# Arduino-RedBoard.net
KiCad netlist of a schematic drawn in Altium Designer
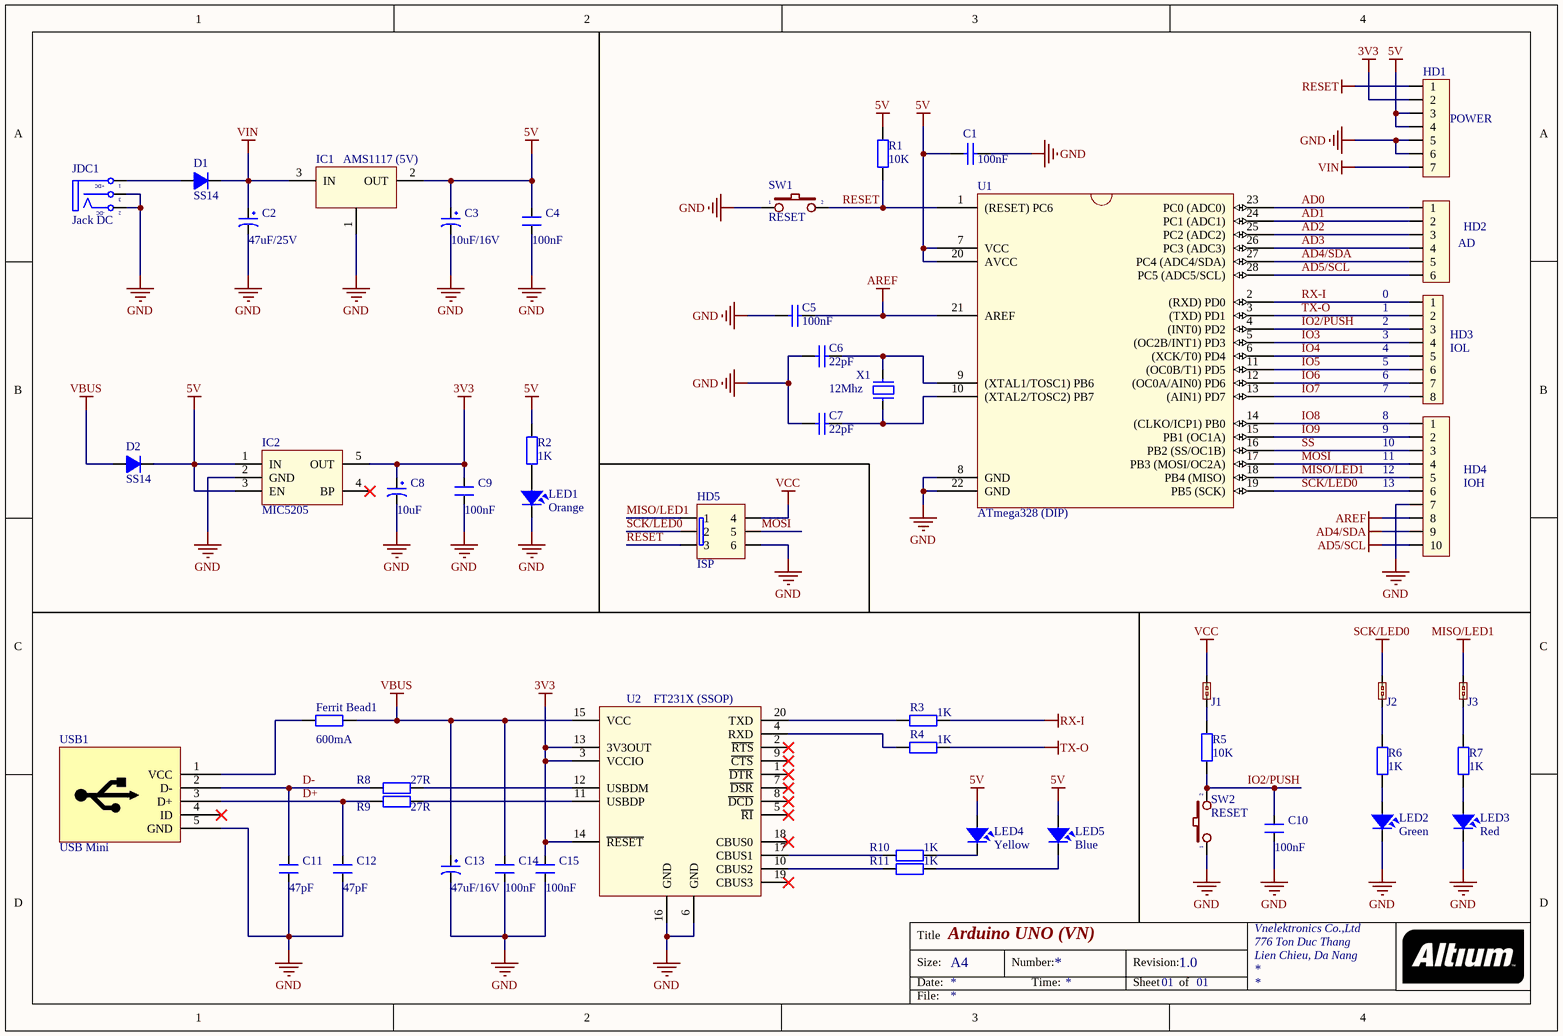
[diagram p0: Arduino-RedBoard.SchDoc]

(export (version "E")
  (design (tool "Eeschema 10.0.6"))
  (components
    (comp (ref "C1")
      (value "100nF")
      (footprint "C0603")
      (description "CAP NPO CAPNTO 1nF 100V 10%")
      (fields (field (name "Comment") "5AK102KABAA"))
      (libsource (lib "lpson") (part "5AK102KABAA"))
    )
    (comp (ref "C2") (value "47uF/25V") (footprint "C_FK_47UF_25V") (libsource (lib "VNELEK") (part "CP1")))
    (comp (ref "C3")
      (value "10uF/16V")
      (footprint "C0805")
      (description "Cap P  0,1uF < 22uF , 16 - 50V")
      (libsource (lib "VNELEK") (part "CP1"))
    )
    (comp (ref "C4")
      (value "100nF")
      (footprint "C0603")
      (description "Cap np 104 => 105pF")
      (libsource (lib "VNELEK") (part "CN2"))
    )
    (comp (ref "C5")
      (value "100nF")
      (footprint "C0603")
      (description "CAP NPO CAPNTO 1nF 100V 10%")
      (fields (field (name "Comment") "5AK102KABAA"))
      (libsource (lib "lpson") (part "5AK102KABAA"))
    )
    (comp (ref "C6")
      (value "22pF")
      (footprint "C0603")
      (description "CAP NPO CAPNTO 1nF 100V 10%")
      (fields (field (name "Comment") "5AK102KABAA"))
      (libsource (lib "lpson") (part "5AK102KABAA"))
    )
    (comp (ref "C7")
      (value "22pF")
      (footprint "C0603")
      (description "CAP NPO CAPNTO 1nF 100V 10%")
      (fields (field (name "Comment") "5AK102KABAA"))
      (libsource (lib "lpson") (part "5AK102KABAA"))
    )
    (comp (ref "C8")
      (value "10uF")
      (footprint "C0805")
      (description "Cap P  0,1uF < 22uF , 16 - 50V")
      (libsource (lib "VNELEK") (part "CP1"))
    )
    (comp (ref "C9")
      (value "100nF")
      (footprint "C0603")
      (description "Cap np 104 => 105pF")
      (libsource (lib "VNELEK") (part "CN2"))
    )
    (comp (ref "C10")
      (value "100nF")
      (footprint "C0603")
      (description "Cap np 104 => 105pF")
      (libsource (lib "VNELEK") (part "CN2"))
    )
    (comp (ref "C11")
      (value "47pF")
      (footprint "C0805")
      (description "Cap np 104 => 105pF")
      (libsource (lib "VNELEK") (part "CN2"))
    )
    (comp (ref "C12")
      (value "47pF")
      (footprint "C0805")
      (description "Cap np 104 => 105pF")
      (libsource (lib "VNELEK") (part "CN2"))
    )
    (comp (ref "C13") (value "47uF/16V") (footprint "C_FK_47UF_16V") (libsource (lib "VNELEK") (part "CP1")))
    (comp (ref "C14")
      (value "100nF")
      (footprint "C0603")
      (description "Cap np 104 => 105pF")
      (libsource (lib "VNELEK") (part "CN2"))
    )
    (comp (ref "C15")
      (value "100nF")
      (footprint "C0603")
      (description "Cap np 104 => 105pF")
      (libsource (lib "VNELEK") (part "CN2"))
    )
    (comp (ref "D1")
      (value "SS14")
      (footprint "SS14")
      (description "Diode 1A")
      (libsource (lib "VNELEK") (part "D1A"))
    )
    (comp (ref "D2")
      (value "SS14")
      (footprint "SS14")
      (description "Diode 1A")
      (libsource (lib "VNELEK") (part "D1A"))
    )
    (comp (ref "Ferrit Bead1")
      (value "600mA")
      (footprint "CB2012")
      (description "Ferrit Bead")
      (libsource (lib "") (part "Res2_2"))
    )
    (comp (ref "HD1")
      (value "POWER")
      (footprint "Header_7")
      (description "Header 7")
      (libsource (lib "Tran Tuan") (part "Hed7"))
    )
    (comp (ref "HD2")
      (value "AD")
      (footprint "Header_6")
      (description "Header 6")
      (libsource (lib "Tran Tuan") (part "Hed6"))
    )
    (comp (ref "HD3")
      (value "IOL")
      (footprint "Header_8")
      (description "Hedear 8")
      (fields (field (name "CREAT BY") "VanDungEvn@Gmail.com"))
      (libsource (lib "VNELEK") (part "Hed8"))
    )
    (comp (ref "HD4")
      (value "IOH")
      (footprint "Header_10")
      (description "Header 10")
      (libsource (lib "Tran Tuan") (part "Hed10"))
    )
    (comp (ref "HD5")
      (value "ISP")
      (footprint "Header_3x2")
      (description "Header 3x2")
      (libsource (lib "Tran Tuan") (part "HED3x2"))
    )
    (comp (ref "IC1")
      (value "AMS1117 (5V)")
      (footprint "AMS1117-5.0V")
      (description "1A LOW DROPOUT VOLTAGE REGULATOR")
      (libsource (lib "Tran Tuan") (part "AMS1117"))
    )
    (comp (ref "IC2")
      (value "MIC5205")
      (footprint "MIC5205")
      (description "150mA Low  -  Noise LDO Regulator")
      (libsource (lib "Tran Tuan") (part "MIC5205"))
    )
    (comp (ref "J1")
      (value "Short Jump")
      (footprint "Header_2")
      (libsource (lib "Tran Tuan") (part "ShortJump"))
    )
    (comp (ref "J2")
      (value "Short Jump")
      (footprint "Header_2")
      (libsource (lib "Tran Tuan") (part "ShortJump"))
    )
    (comp (ref "J3")
      (value "Short Jump")
      (footprint "Header_2")
      (libsource (lib "Tran Tuan") (part "ShortJump"))
    )
    (comp (ref "JDC1")
      (value "Jack DC")
      (footprint "DC-IN")
      (description "Jac DC input")
      (libsource (lib "VNELEK") (part "DCIN"))
    )
    (comp (ref "LED1")
      (value "Orange")
      (footprint "Led 0805Y")
      (description "LED Single colour Green and Red")
      (libsource (lib "VNELEK") (part "LED"))
    )
    (comp (ref "LED2")
      (value "Green")
      (footprint "Led 0805G")
      (description "LED Single colour Green and Red")
      (libsource (lib "VNELEK") (part "LED"))
    )
    (comp (ref "LED3")
      (value "Red")
      (footprint "Led 0805R")
      (description "LED Single colour Green and Red")
      (libsource (lib "VNELEK") (part "LED"))
    )
    (comp (ref "LED4")
      (value "Yellow")
      (footprint "Led 0805Y")
      (description "LED Single colour Green and Red")
      (libsource (lib "VNELEK") (part "LED"))
    )
    (comp (ref "LED5")
      (value "Blue")
      (footprint "Led 0805BL")
      (description "LED Single colour Green and Red")
      (libsource (lib "VNELEK") (part "LED"))
    )
    (comp (ref "R1")
      (value "10K")
      (footprint "RESC2012L")
      (description "Resistor")
      (fields (field (name "Comment") "Res2") (field (name "PUBLISHER") "Altium Limited"))
      (libsource (lib "Miscellaneous Devices") (part "Res2"))
    )
    (comp (ref "R2")
      (value "1K")
      (footprint "RESC2012L")
      (description "Resistor")
      (fields (field (name "Comment") "Res2") (field (name "PUBLISHER") "Altium Limited"))
      (libsource (lib "Miscellaneous Devices") (part "Res2"))
    )
    (comp (ref "R3")
      (value "1K")
      (footprint "RESC2012L")
      (description "Resistor")
      (fields (field (name "Comment") "Res2") (field (name "PUBLISHER") "Altium Limited"))
      (libsource (lib "") (part "Res2_2"))
    )
    (comp (ref "R4")
      (value "1K")
      (footprint "RESC2012L")
      (description "Resistor")
      (fields (field (name "Comment") "Res2") (field (name "PUBLISHER") "Altium Limited"))
      (libsource (lib "") (part "Res2_2"))
    )
    (comp (ref "R5")
      (value "10K")
      (footprint "RESC2012L")
      (description "Resistor")
      (fields (field (name "Comment") "Res2") (field (name "PUBLISHER") "Altium Limited"))
      (libsource (lib "Miscellaneous Devices") (part "Res2"))
    )
    (comp (ref "R6")
      (value "1K")
      (footprint "RESC2012L")
      (description "Resistor")
      (fields (field (name "Comment") "Res2") (field (name "PUBLISHER") "Altium Limited"))
      (libsource (lib "Miscellaneous Devices") (part "Res2"))
    )
    (comp (ref "R7")
      (value "1K")
      (footprint "RESC2012L")
      (description "Resistor")
      (fields (field (name "Comment") "Res2") (field (name "PUBLISHER") "Altium Limited"))
      (libsource (lib "Miscellaneous Devices") (part "Res2"))
    )
    (comp (ref "R8")
      (value "27R")
      (footprint "RESC2012L")
      (description "Resistor")
      (fields (field (name "Comment") "Res2") (field (name "PUBLISHER") "Altium Limited"))
      (libsource (lib "") (part "Res2_1"))
    )
    (comp (ref "R9")
      (value "27R")
      (footprint "RESC2012L")
      (description "Resistor")
      (fields (field (name "Comment") "Res2") (field (name "PUBLISHER") "Altium Limited"))
      (libsource (lib "") (part "Res2_1"))
    )
    (comp (ref "R10")
      (value "1K")
      (footprint "RESC2012L")
      (description "Resistor")
      (fields (field (name "Comment") "Res2") (field (name "PUBLISHER") "Altium Limited"))
      (libsource (lib "") (part "Res2_1"))
    )
    (comp (ref "R11")
      (value "1K")
      (footprint "RESC2012L")
      (description "Resistor")
      (fields (field (name "Comment") "Res2") (field (name "PUBLISHER") "Altium Limited"))
      (libsource (lib "") (part "Res2_1"))
    )
    (comp (ref "SW1")
      (value "RESET")
      (footprint "BUTTON 2PIN TRON")
      (description "Switch button 2 pin")
      (libsource (lib "VNELEK") (part "SW2"))
    )
    (comp (ref "SW2")
      (value "RESET")
      (footprint "BUTTON 2PIN TRON")
      (description "Switch button 2 pin")
      (libsource (lib "VNELEK") (part "SW2"))
    )
    (comp (ref "U1")
      (value "ATmega328 (DIP)")
      (footprint "ATmega328 (DIP)")
      (description "Atmel 8-bit Microcontroller")
      (libsource (lib "Tran Tuan") (part "ATmega328_1"))
    )
    (comp (ref "U2")
      (value "FT231X (SSOP)")
      (footprint "SSOP 20")
      (description "FT231Z (SSOP) - USB to UART")
      (libsource (lib "Tran Tuan") (part "FT231X"))
    )
    (comp (ref "USB1") (value "USB Mini") (footprint "USBMNIB") (libsource (lib "VNELEK") (part "USB_M")))
    (comp (ref "X1")
      (value "12Mhz")
      (footprint "CRYSTAL")
      (description "Crystal For all Crystal 2pin.")
      (libsource (lib "lpson") (part "XT2"))
    )
  )
  (nets
    (net (code "1") (name "/AD0") (class "Default")
      (node (ref "HD2") (pin "1") (pinfunction "1_1") (pintype "passive"))
      (node (ref "U1") (pin "23") (pinfunction "PC0_(ADC0)_23") (pintype "bidirectional"))
    )
    (net (code "2") (name "/AD1") (class "Default")
      (node (ref "HD2") (pin "2") (pinfunction "2_2") (pintype "passive"))
      (node (ref "U1") (pin "24") (pinfunction "PC1_(ADC1)_24") (pintype "bidirectional"))
    )
    (net (code "3") (name "/AD2") (class "Default")
      (node (ref "HD2") (pin "3") (pinfunction "3_3") (pintype "passive"))
      (node (ref "U1") (pin "25") (pinfunction "PC2_(ADC2)_25") (pintype "bidirectional"))
    )
    (net (code "4") (name "/AD3") (class "Default")
      (node (ref "HD2") (pin "4") (pinfunction "4_4") (pintype "passive"))
      (node (ref "U1") (pin "26") (pinfunction "PC3_(ADC3)_26") (pintype "bidirectional"))
    )
    (net (code "5") (name "/D+") (class "Default")
      (node (ref "C12") (pin "2") (pinfunction "2_2") (pintype "passive"))
      (node (ref "R9") (pin "2") (pinfunction "2_2") (pintype "passive"))
      (node (ref "USB1") (pin "3") (pinfunction "D+_3") (pintype "passive"))
    )
    (net (code "6") (name "/D-") (class "Default")
      (node (ref "C11") (pin "2") (pinfunction "2_2") (pintype "passive"))
      (node (ref "R8") (pin "2") (pinfunction "2_2") (pintype "passive"))
      (node (ref "USB1") (pin "2") (pinfunction "D-_2") (pintype "passive"))
    )
    (net (code "7") (name "/IO2{slash}PUSH") (class "Default")
      (node (ref "C10") (pin "2") (pinfunction "2_2") (pintype "passive"))
      (node (ref "HD3") (pin "3") (pinfunction "3_3") (pintype "passive"))
      (node (ref "R5") (pin "1") (pinfunction "1_1") (pintype "passive"))
      (node (ref "SW2") (pin "2") (pinfunction "2_2") (pintype "passive"))
      (node (ref "U1") (pin "4") (pinfunction "(INT0)_PD2_4") (pintype "bidirectional"))
    )
    (net (code "8") (name "/IO3") (class "Default")
      (node (ref "HD3") (pin "4") (pinfunction "4_4") (pintype "passive"))
      (node (ref "U1") (pin "5") (pinfunction "(OC2B/INT1)_PD3_5") (pintype "bidirectional"))
    )
    (net (code "9") (name "/IO4") (class "Default")
      (node (ref "HD3") (pin "5") (pinfunction "5_5") (pintype "passive"))
      (node (ref "U1") (pin "6") (pinfunction "(XCK/T0)_PD4_6") (pintype "bidirectional"))
    )
    (net (code "10") (name "/IO5") (class "Default")
      (node (ref "HD3") (pin "6") (pinfunction "6_6") (pintype "passive"))
      (node (ref "U1") (pin "11") (pinfunction "(OC0B/T1)_PD5_11") (pintype "bidirectional"))
    )
    (net (code "11") (name "/IO6") (class "Default")
      (node (ref "HD3") (pin "7") (pinfunction "7_7") (pintype "passive"))
      (node (ref "U1") (pin "12") (pinfunction "(OC0A/AIN0)_PD6_12") (pintype "bidirectional"))
    )
    (net (code "12") (name "/IO7") (class "Default")
      (node (ref "HD3") (pin "8") (pinfunction "8_8") (pintype "passive"))
      (node (ref "U1") (pin "13") (pinfunction "(AIN1)_PD7_13") (pintype "bidirectional"))
    )
    (net (code "13") (name "/IO8") (class "Default")
      (node (ref "HD4") (pin "1") (pinfunction "1_1") (pintype "passive"))
      (node (ref "U1") (pin "14") (pinfunction "(CLKO/ICP1)_PB0_14") (pintype "bidirectional"))
    )
    (net (code "14") (name "/IO9") (class "Default")
      (node (ref "HD4") (pin "2") (pinfunction "2_2") (pintype "passive"))
      (node (ref "U1") (pin "15") (pinfunction "PB1_(OC1A)_15") (pintype "bidirectional"))
    )
    (net (code "15") (name "/MOSI") (class "Default")
      (node (ref "HD4") (pin "4") (pinfunction "4_4") (pintype "passive"))
      (node (ref "HD5") (pin "5") (pinfunction "5_5") (pintype "passive"))
      (node (ref "U1") (pin "17") (pinfunction "PB3_(MOSI/OC2A)_17") (pintype "bidirectional"))
    )
    (net (code "16") (name "/SS") (class "Default")
      (node (ref "HD4") (pin "3") (pinfunction "3_3") (pintype "passive"))
      (node (ref "U1") (pin "16") (pinfunction "PB2_(SS/OC1B)_16") (pintype "bidirectional"))
    )
    (net (code "17") (name "3V3") (class "Default")
      (node (ref "C15") (pin "2") (pinfunction "2_2") (pintype "passive"))
      (node (ref "C8") (pin "1") (pinfunction "1_1") (pintype "passive"))
      (node (ref "C9") (pin "2") (pinfunction "2_2") (pintype "passive"))
      (node (ref "HD1") (pin "2") (pinfunction "2_2") (pintype "passive"))
      (node (ref "IC2") (pin "5") (pinfunction "OUT_5") (pintype "passive"))
      (node (ref "U2") (pin "13") (pinfunction "3V3OUT_13") (pintype "passive"))
      (node (ref "U2") (pin "14") (pinfunction "~{RESET}_14") (pintype "passive"))
      (node (ref "U2") (pin "3") (pinfunction "VCCIO_3") (pintype "passive"))
    )
    (net (code "18") (name "5V") (class "Default")
      (node (ref "C1") (pin "2") (pinfunction "2_2") (pintype "passive"))
      (node (ref "C3") (pin "1") (pinfunction "1_1") (pintype "passive"))
      (node (ref "C4") (pin "2") (pinfunction "2_2") (pintype "passive"))
      (node (ref "D2") (pin "2") (pinfunction "K_2") (pintype "passive"))
      (node (ref "HD1") (pin "3") (pinfunction "3_3") (pintype "passive"))
      (node (ref "HD1") (pin "4") (pinfunction "4_4") (pintype "passive"))
      (node (ref "IC1") (pin "2") (pinfunction "OUT_2") (pintype "passive"))
      (node (ref "IC2") (pin "1") (pinfunction "IN_1") (pintype "passive"))
      (node (ref "IC2") (pin "3") (pinfunction "EN_3") (pintype "passive"))
      (node (ref "LED4") (pin "1") (pinfunction "1_1") (pintype "passive"))
      (node (ref "LED5") (pin "1") (pinfunction "1_1") (pintype "passive"))
      (node (ref "R1") (pin "2") (pinfunction "2_2") (pintype "passive"))
      (node (ref "R2") (pin "2") (pinfunction "2_2") (pintype "passive"))
      (node (ref "U1") (pin "20") (pinfunction "AVCC_20") (pintype "passive"))
      (node (ref "U1") (pin "7") (pinfunction "VCC_7") (pintype "passive"))
    )
    (net (code "19") (name "AD4{slash}SDA") (class "Default")
      (node (ref "HD2") (pin "5") (pinfunction "5_5") (pintype "passive"))
      (node (ref "HD4") (pin "9") (pinfunction "9_9") (pintype "passive"))
      (node (ref "U1") (pin "27") (pinfunction "PC4_(ADC4/SDA)_27") (pintype "bidirectional"))
    )
    (net (code "20") (name "AD5{slash}SCL") (class "Default")
      (node (ref "HD2") (pin "6") (pinfunction "6_6") (pintype "passive"))
      (node (ref "HD4") (pin "10") (pinfunction "10_10") (pintype "passive"))
      (node (ref "U1") (pin "28") (pinfunction "PC5_(ADC5/SCL)_28") (pintype "bidirectional"))
    )
    (net (code "21") (name "AREF") (class "Default")
      (node (ref "C5") (pin "2") (pinfunction "2_2") (pintype "passive"))
      (node (ref "HD4") (pin "8") (pinfunction "8_8") (pintype "passive"))
      (node (ref "U1") (pin "21") (pinfunction "AREF_21") (pintype "passive"))
    )
    (net (code "22") (name "GND") (class "Default")
      (node (ref "C1") (pin "1") (pinfunction "1_1") (pintype "passive"))
      (node (ref "C10") (pin "1") (pinfunction "1_1") (pintype "passive"))
      (node (ref "C11") (pin "1") (pinfunction "1_1") (pintype "passive"))
      (node (ref "C12") (pin "1") (pinfunction "1_1") (pintype "passive"))
      (node (ref "C13") (pin "2") (pinfunction "2_2") (pintype "passive"))
      (node (ref "C14") (pin "2") (pinfunction "2_2") (pintype "passive"))
      (node (ref "C15") (pin "1") (pinfunction "1_1") (pintype "passive"))
      (node (ref "C2") (pin "2") (pinfunction "2_2") (pintype "passive"))
      (node (ref "C3") (pin "2") (pinfunction "2_2") (pintype "passive"))
      (node (ref "C4") (pin "1") (pinfunction "1_1") (pintype "passive"))
      (node (ref "C5") (pin "1") (pinfunction "1_1") (pintype "passive"))
      (node (ref "C6") (pin "1") (pinfunction "1_1") (pintype "passive"))
      (node (ref "C7") (pin "1") (pinfunction "1_1") (pintype "passive"))
      (node (ref "C8") (pin "2") (pinfunction "2_2") (pintype "passive"))
      (node (ref "C9") (pin "1") (pinfunction "1_1") (pintype "passive"))
      (node (ref "HD1") (pin "5") (pinfunction "5_5") (pintype "passive"))
      (node (ref "HD1") (pin "6") (pinfunction "6_6") (pintype "passive"))
      (node (ref "HD4") (pin "7") (pinfunction "7_7") (pintype "passive"))
      (node (ref "HD5") (pin "6") (pinfunction "6_6") (pintype "passive"))
      (node (ref "IC1") (pin "1") (pinfunction "GND_1") (pintype "passive"))
      (node (ref "IC2") (pin "2") (pinfunction "GND_2") (pintype "passive"))
      (node (ref "JDC1") (pin "2") (pinfunction "TN_2") (pintype "passive"))
      (node (ref "JDC1") (pin "3") (pinfunction "S_3") (pintype "power_in"))
      (node (ref "LED1") (pin "2") (pinfunction "2_2") (pintype "passive"))
      (node (ref "LED2") (pin "2") (pinfunction "2_2") (pintype "passive"))
      (node (ref "LED3") (pin "2") (pinfunction "2_2") (pintype "passive"))
      (node (ref "SW1") (pin "1") (pinfunction "1_1") (pintype "passive"))
      (node (ref "SW2") (pin "1") (pinfunction "1_1") (pintype "passive"))
      (node (ref "U1") (pin "22") (pinfunction "GND_22") (pintype "passive"))
      (node (ref "U1") (pin "8") (pinfunction "GND_8") (pintype "passive"))
      (node (ref "U2") (pin "16") (pinfunction "GND_16") (pintype "passive"))
      (node (ref "U2") (pin "6") (pinfunction "GND_6") (pintype "passive"))
      (node (ref "USB1") (pin "5") (pinfunction "GND_5") (pintype "passive"))
    )
    (net (code "23") (name "MISO{slash}LED1") (class "Default")
      (node (ref "HD4") (pin "5") (pinfunction "5_5") (pintype "passive"))
      (node (ref "HD5") (pin "1") (pinfunction "1_1") (pintype "passive"))
      (node (ref "J3") (pin "2") (pinfunction "2_2") (pintype "passive"))
      (node (ref "U1") (pin "18") (pinfunction "PB4_(MISO)_18") (pintype "bidirectional"))
    )
    (net (code "24") (name "Net-(D1-A)") (class "Default")
      (node (ref "D1") (pin "1") (pinfunction "A_1") (pintype "passive"))
      (node (ref "JDC1") (pin "1") (pinfunction "T_1") (pintype "passive"))
    )
    (net (code "25") (name "Net-(J1-Pad1)") (class "Default")
      (node (ref "J1") (pin "1") (pinfunction "1_1") (pintype "passive"))
      (node (ref "R5") (pin "2") (pinfunction "2_2") (pintype "passive"))
    )
    (net (code "26") (name "Net-(J2-Pad1)") (class "Default")
      (node (ref "J2") (pin "1") (pinfunction "1_1") (pintype "passive"))
      (node (ref "R6") (pin "2") (pinfunction "2_2") (pintype "passive"))
    )
    (net (code "27") (name "Net-(J3-Pad1)") (class "Default")
      (node (ref "J3") (pin "1") (pinfunction "1_1") (pintype "passive"))
      (node (ref "R7") (pin "2") (pinfunction "2_2") (pintype "passive"))
    )
    (net (code "28") (name "Net-(LED1-Pad1)") (class "Default")
      (node (ref "LED1") (pin "1") (pinfunction "1_1") (pintype "passive"))
      (node (ref "R2") (pin "1") (pinfunction "1_1") (pintype "passive"))
    )
    (net (code "29") (name "Net-(LED2-Pad1)") (class "Default")
      (node (ref "LED2") (pin "1") (pinfunction "1_1") (pintype "passive"))
      (node (ref "R6") (pin "1") (pinfunction "1_1") (pintype "passive"))
    )
    (net (code "30") (name "Net-(LED3-Pad1)") (class "Default")
      (node (ref "LED3") (pin "1") (pinfunction "1_1") (pintype "passive"))
      (node (ref "R7") (pin "1") (pinfunction "1_1") (pintype "passive"))
    )
    (net (code "31") (name "Net-(LED4-Pad2)") (class "Default")
      (node (ref "LED4") (pin "2") (pinfunction "2_2") (pintype "passive"))
      (node (ref "R10") (pin "1") (pinfunction "1_1") (pintype "passive"))
    )
    (net (code "32") (name "Net-(LED5-Pad2)") (class "Default")
      (node (ref "LED5") (pin "2") (pinfunction "2_2") (pintype "passive"))
      (node (ref "R11") (pin "1") (pinfunction "1_1") (pintype "passive"))
    )
    (net (code "33") (name "Net-(U1-(XTAL1{slash}TOSC1)_PB6)") (class "Default")
      (node (ref "C6") (pin "2") (pinfunction "2_2") (pintype "passive"))
      (node (ref "U1") (pin "9") (pinfunction "(XTAL1/TOSC1)_PB6_9") (pintype "passive"))
      (node (ref "X1") (pin "2") (pinfunction "2_2") (pintype "passive"))
    )
    (net (code "34") (name "Net-(U1-(XTAL2{slash}TOSC2)_PB7)") (class "Default")
      (node (ref "C7") (pin "2") (pinfunction "2_2") (pintype "passive"))
      (node (ref "U1") (pin "10") (pinfunction "(XTAL2/TOSC2)_PB7_10") (pintype "passive"))
      (node (ref "X1") (pin "1") (pinfunction "1_1") (pintype "passive"))
    )
    (net (code "35") (name "Net-(U2-CBUS1)") (class "Default")
      (node (ref "R10") (pin "2") (pinfunction "2_2") (pintype "passive"))
      (node (ref "U2") (pin "17") (pinfunction "CBUS1_17") (pintype "passive"))
    )
    (net (code "36") (name "Net-(U2-CBUS2)") (class "Default")
      (node (ref "R11") (pin "2") (pinfunction "2_2") (pintype "passive"))
      (node (ref "U2") (pin "10") (pinfunction "CBUS2_10") (pintype "passive"))
    )
    (net (code "37") (name "Net-(U2-RXD)") (class "Default")
      (node (ref "R4") (pin "1") (pinfunction "1_1") (pintype "passive"))
      (node (ref "U2") (pin "4") (pinfunction "RXD_4") (pintype "passive"))
    )
    (net (code "38") (name "Net-(U2-TXD)") (class "Default")
      (node (ref "R3") (pin "1") (pinfunction "1_1") (pintype "passive"))
      (node (ref "U2") (pin "20") (pinfunction "TXD_20") (pintype "passive"))
    )
    (net (code "39") (name "Net-(U2-USBDM)") (class "Default")
      (node (ref "R8") (pin "1") (pinfunction "1_1") (pintype "passive"))
      (node (ref "U2") (pin "12") (pinfunction "USBDM_12") (pintype "passive"))
    )
    (net (code "40") (name "Net-(U2-USBDP)") (class "Default")
      (node (ref "R9") (pin "1") (pinfunction "1_1") (pintype "passive"))
      (node (ref "U2") (pin "11") (pinfunction "USBDP_11") (pintype "passive"))
    )
    (net (code "41") (name "Net-(USB1-VCC)") (class "Default")
      (node (ref "Ferrit Bead1") (pin "1") (pinfunction "1_1") (pintype "passive"))
      (node (ref "USB1") (pin "1") (pinfunction "VCC_1") (pintype "passive"))
    )
    (net (code "42") (name "RESET") (class "Default")
      (node (ref "HD1") (pin "1") (pinfunction "1_1") (pintype "passive"))
      (node (ref "HD5") (pin "3") (pinfunction "3_3") (pintype "passive"))
      (node (ref "R1") (pin "1") (pinfunction "1_1") (pintype "passive"))
      (node (ref "SW1") (pin "2") (pinfunction "2_2") (pintype "passive"))
      (node (ref "U1") (pin "1") (pinfunction "(RESET)_PC6_1") (pintype "passive"))
    )
    (net (code "43") (name "RX-I") (class "Default")
      (node (ref "HD3") (pin "1") (pinfunction "1_1") (pintype "passive"))
      (node (ref "R3") (pin "2") (pinfunction "2_2") (pintype "passive"))
      (node (ref "U1") (pin "2") (pinfunction "(RXD)_PD0_2") (pintype "bidirectional"))
    )
    (net (code "44") (name "SCK{slash}LED0") (class "Default")
      (node (ref "HD4") (pin "6") (pinfunction "6_6") (pintype "passive"))
      (node (ref "HD5") (pin "2") (pinfunction "2_2") (pintype "passive"))
      (node (ref "J2") (pin "2") (pinfunction "2_2") (pintype "passive"))
      (node (ref "U1") (pin "19") (pinfunction "PB5_(SCK)_19") (pintype "bidirectional"))
    )
    (net (code "45") (name "TX-O") (class "Default")
      (node (ref "HD3") (pin "2") (pinfunction "2_2") (pintype "passive"))
      (node (ref "R4") (pin "2") (pinfunction "2_2") (pintype "passive"))
      (node (ref "U1") (pin "3") (pinfunction "(TXD)_PD1_3") (pintype "bidirectional"))
    )
    (net (code "46") (name "VBUS") (class "Default")
      (node (ref "C13") (pin "1") (pinfunction "1_1") (pintype "passive"))
      (node (ref "C14") (pin "1") (pinfunction "1_1") (pintype "passive"))
      (node (ref "D2") (pin "1") (pinfunction "A_1") (pintype "passive"))
      (node (ref "Ferrit Bead1") (pin "2") (pinfunction "2_2") (pintype "passive"))
      (node (ref "U2") (pin "15") (pinfunction "VCC_15") (pintype "passive"))
    )
    (net (code "47") (name "VCC") (class "Default")
      (node (ref "HD5") (pin "4") (pinfunction "4_4") (pintype "passive"))
      (node (ref "J1") (pin "2") (pinfunction "2_2") (pintype "passive"))
    )
    (net (code "48") (name "VIN") (class "Default")
      (node (ref "C2") (pin "1") (pinfunction "1_1") (pintype "passive"))
      (node (ref "D1") (pin "2") (pinfunction "K_2") (pintype "passive"))
      (node (ref "HD1") (pin "7") (pinfunction "7_7") (pintype "passive"))
      (node (ref "IC1") (pin "3") (pinfunction "IN_3") (pintype "passive"))
    )
    (net (code "49") (name "unconnected-(IC2-BP-Pad4)") (class "Default")
      (node (ref "IC2") (pin "4") (pinfunction "BP_4") (pintype "passive+no_connect"))
    )
    (net (code "50") (name "unconnected-(U2-CBUS0-Pad18)") (class "Default")
      (node (ref "U2") (pin "18") (pinfunction "CBUS0_18") (pintype "passive+no_connect"))
    )
    (net (code "51") (name "unconnected-(U2-CBUS3-Pad19)") (class "Default")
      (node (ref "U2") (pin "19") (pinfunction "CBUS3_19") (pintype "passive+no_connect"))
    )
    (net (code "52") (name "unconnected-(U2-~{CTS}-Pad9)") (class "Default")
      (node (ref "U2") (pin "9") (pinfunction "~{CTS}_9") (pintype "passive+no_connect"))
    )
    (net (code "53") (name "unconnected-(U2-~{DCD}-Pad8)") (class "Default")
      (node (ref "U2") (pin "8") (pinfunction "~{DCD}_8") (pintype "passive+no_connect"))
    )
    (net (code "54") (name "unconnected-(U2-~{DSR}-Pad7)") (class "Default")
      (node (ref "U2") (pin "7") (pinfunction "~{DSR}_7") (pintype "passive+no_connect"))
    )
    (net (code "55") (name "unconnected-(U2-~{DTR}-Pad1)") (class "Default")
      (node (ref "U2") (pin "1") (pinfunction "~{DTR}_1") (pintype "passive+no_connect"))
    )
    (net (code "56") (name "unconnected-(U2-~{RI}-Pad5)") (class "Default")
      (node (ref "U2") (pin "5") (pinfunction "~{RI}_5") (pintype "passive+no_connect"))
    )
    (net (code "57") (name "unconnected-(U2-~{RTS}-Pad2)") (class "Default")
      (node (ref "U2") (pin "2") (pinfunction "~{RTS}_2") (pintype "passive+no_connect"))
    )
    (net (code "58") (name "unconnected-(USB1-ID-Pad4)") (class "Default")
      (node (ref "USB1") (pin "4") (pinfunction "ID_4") (pintype "passive+no_connect"))
    )
  )
)
